# final_project_schem.net
KiCad netlist of a schematic drawn in EAGLE
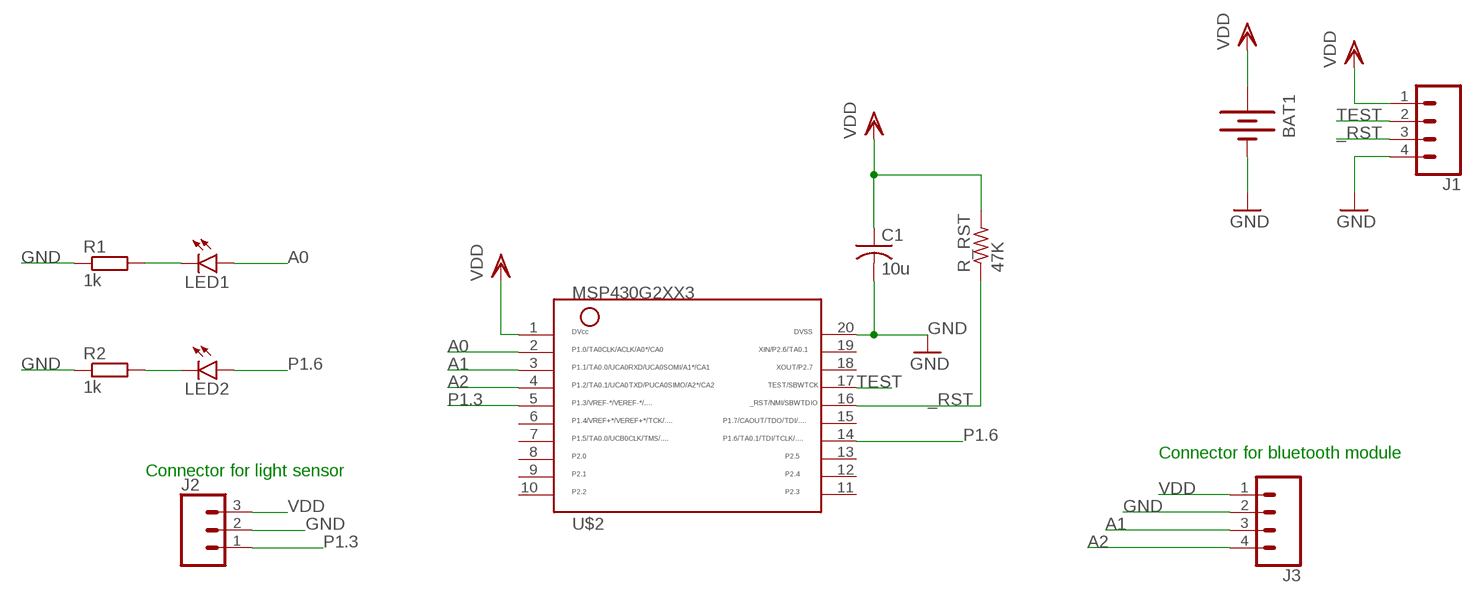
[diagram p0: schematic, sheet 1]

(export (version "E")
  (design (tool "Eeschema 10.0.6"))
  (components
    (comp (ref "BAT1")
      (value "BATTERYBU2032SM")
      (footprint "eagle-import:BU2032SM")
      (libsource (lib "eagle-import") (part "BATTERYBU2032SM"))
    )
    (comp (ref "C1")
      (value "10u")
      (footprint "eagle-import:C1206")
      (libsource (lib "eagle-import") (part "C-USC1206"))
    )
    (comp (ref "J1")
      (value "CONN_04LOCK")
      (footprint "eagle-import:1X04_LOCK")
      (libsource (lib "eagle-import") (part "CONN_04LOCK"))
    )
    (comp (ref "J2")
      (value "CONN_03LOCK")
      (footprint "eagle-import:1X03_LOCK")
      (libsource (lib "eagle-import") (part "CONN_03LOCK"))
    )
    (comp (ref "J3")
      (value "CONN_04LOCK")
      (footprint "eagle-import:1X04_LOCK")
      (libsource (lib "eagle-import") (part "CONN_04LOCK"))
    )
    (comp (ref "LED1")
      (value "LEDCHIPLED_0805")
      (footprint "eagle-import:CHIPLED_0805")
      (libsource (lib "eagle-import") (part "LEDCHIPLED_0805"))
    )
    (comp (ref "LED2")
      (value "LEDCHIPLED_0805")
      (footprint "eagle-import:CHIPLED_0805")
      (libsource (lib "eagle-import") (part "LEDCHIPLED_0805"))
    )
    (comp (ref "R1")
      (value "1k")
      (footprint "eagle-import:R0603")
      (libsource (lib "eagle-import") (part "R-EU_R0603"))
    )
    (comp (ref "R2")
      (value "1k")
      (footprint "eagle-import:R0603")
      (libsource (lib "eagle-import") (part "R-EU_R0603"))
    )
    (comp (ref "R_RST")
      (value "47K")
      (footprint "eagle-import:R1206")
      (libsource (lib "eagle-import") (part "R-US_R1206"))
    )
    (comp (ref "U$2")
      (value "MSP430G2XX3TSSOP")
      (footprint "eagle-import:PW20")
      (libsource (lib "eagle-import") (part "MSP430G2XX3TSSOP"))
    )
  )
  (nets
    (net (code "1") (name "/A0") (class "Default")
      (node (ref "LED1") (pin "A") (pinfunction "A_A") (pintype "passive"))
      (node (ref "U$2") (pin "2") (pinfunction "2_2") (pintype "bidirectional"))
    )
    (net (code "2") (name "/A1") (class "Default")
      (node (ref "J3") (pin "3") (pinfunction "3_3") (pintype "passive"))
      (node (ref "U$2") (pin "3") (pinfunction "3_3") (pintype "bidirectional"))
    )
    (net (code "3") (name "/A2") (class "Default")
      (node (ref "J3") (pin "4") (pinfunction "4_4") (pintype "passive"))
      (node (ref "U$2") (pin "4") (pinfunction "4_4") (pintype "bidirectional"))
    )
    (net (code "4") (name "/P1.3") (class "Default")
      (node (ref "J2") (pin "1") (pinfunction "1_1") (pintype "passive"))
      (node (ref "U$2") (pin "5") (pinfunction "5_5") (pintype "bidirectional"))
    )
    (net (code "5") (name "/P1.6") (class "Default")
      (node (ref "LED2") (pin "A") (pinfunction "A_A") (pintype "passive"))
      (node (ref "U$2") (pin "14") (pinfunction "14_14") (pintype "bidirectional"))
    )
    (net (code "6") (name "/TEST") (class "Default")
      (node (ref "J1") (pin "2") (pinfunction "2_2") (pintype "passive"))
      (node (ref "U$2") (pin "17") (pinfunction "17_17") (pintype "bidirectional"))
    )
    (net (code "7") (name "/_RST") (class "Default")
      (node (ref "J1") (pin "3") (pinfunction "3_3") (pintype "passive"))
      (node (ref "R_RST") (pin "1") (pinfunction "1_1") (pintype "passive"))
      (node (ref "U$2") (pin "16") (pinfunction "16_16") (pintype "bidirectional"))
    )
    (net (code "8") (name "GND") (class "Default")
      (node (ref "BAT1") (pin "P$2") (pinfunction "-_P$2") (pintype "power_in"))
      (node (ref "C1") (pin "2") (pinfunction "2_2") (pintype "passive"))
      (node (ref "J1") (pin "4") (pinfunction "4_4") (pintype "passive"))
      (node (ref "J2") (pin "2") (pinfunction "2_2") (pintype "passive"))
      (node (ref "J3") (pin "2") (pinfunction "2_2") (pintype "passive"))
      (node (ref "R1") (pin "1") (pinfunction "1_1") (pintype "passive"))
      (node (ref "R2") (pin "1") (pinfunction "1_1") (pintype "passive"))
      (node (ref "U$2") (pin "20") (pinfunction "20_20") (pintype "bidirectional"))
    )
    (net (code "9") (name "Net-(LED1-PadC)") (class "Default")
      (node (ref "LED1") (pin "C") (pinfunction "C_C") (pintype "passive"))
      (node (ref "R1") (pin "2") (pinfunction "2_2") (pintype "passive"))
    )
    (net (code "10") (name "Net-(LED2-PadC)") (class "Default")
      (node (ref "LED2") (pin "C") (pinfunction "C_C") (pintype "passive"))
      (node (ref "R2") (pin "2") (pinfunction "2_2") (pintype "passive"))
    )
    (net (code "11") (name "VDD") (class "Default")
      (node (ref "BAT1") (pin "P$1") (pinfunction "+_P$1") (pintype "power_in"))
      (node (ref "C1") (pin "1") (pinfunction "1_1") (pintype "passive"))
      (node (ref "J1") (pin "1") (pinfunction "1_1") (pintype "passive"))
      (node (ref "J2") (pin "3") (pinfunction "3_3") (pintype "passive"))
      (node (ref "J3") (pin "1") (pinfunction "1_1") (pintype "passive"))
      (node (ref "R_RST") (pin "2") (pinfunction "2_2") (pintype "passive"))
      (node (ref "U$2") (pin "1") (pinfunction "1_1") (pintype "bidirectional"))
    )
    (net (code "12") (name "unconnected-(U$2-Pad6)") (class "Default")
      (node (ref "U$2") (pin "6") (pinfunction "6_6") (pintype "bidirectional"))
    )
    (net (code "13") (name "unconnected-(U$2-Pad7)") (class "Default")
      (node (ref "U$2") (pin "7") (pinfunction "7_7") (pintype "bidirectional"))
    )
    (net (code "14") (name "unconnected-(U$2-Pad8)") (class "Default")
      (node (ref "U$2") (pin "8") (pinfunction "8_8") (pintype "bidirectional"))
    )
    (net (code "15") (name "unconnected-(U$2-Pad9)") (class "Default")
      (node (ref "U$2") (pin "9") (pinfunction "9_9") (pintype "bidirectional"))
    )
    (net (code "16") (name "unconnected-(U$2-Pad10)") (class "Default")
      (node (ref "U$2") (pin "10") (pinfunction "10_10") (pintype "bidirectional"))
    )
    (net (code "17") (name "unconnected-(U$2-Pad11)") (class "Default")
      (node (ref "U$2") (pin "11") (pinfunction "11_11") (pintype "bidirectional"))
    )
    (net (code "18") (name "unconnected-(U$2-Pad12)") (class "Default")
      (node (ref "U$2") (pin "12") (pinfunction "12_12") (pintype "bidirectional"))
    )
    (net (code "19") (name "unconnected-(U$2-Pad13)") (class "Default")
      (node (ref "U$2") (pin "13") (pinfunction "13_13") (pintype "bidirectional"))
    )
    (net (code "20") (name "unconnected-(U$2-Pad15)") (class "Default")
      (node (ref "U$2") (pin "15") (pinfunction "15_15") (pintype "bidirectional"))
    )
    (net (code "21") (name "unconnected-(U$2-Pad18)") (class "Default")
      (node (ref "U$2") (pin "18") (pinfunction "18_18") (pintype "bidirectional"))
    )
    (net (code "22") (name "unconnected-(U$2-Pad19)") (class "Default")
      (node (ref "U$2") (pin "19") (pinfunction "19_19") (pintype "bidirectional"))
    )
  )
)
